# sram.net
KiCad netlist of a schematic drawn in Altium Designer
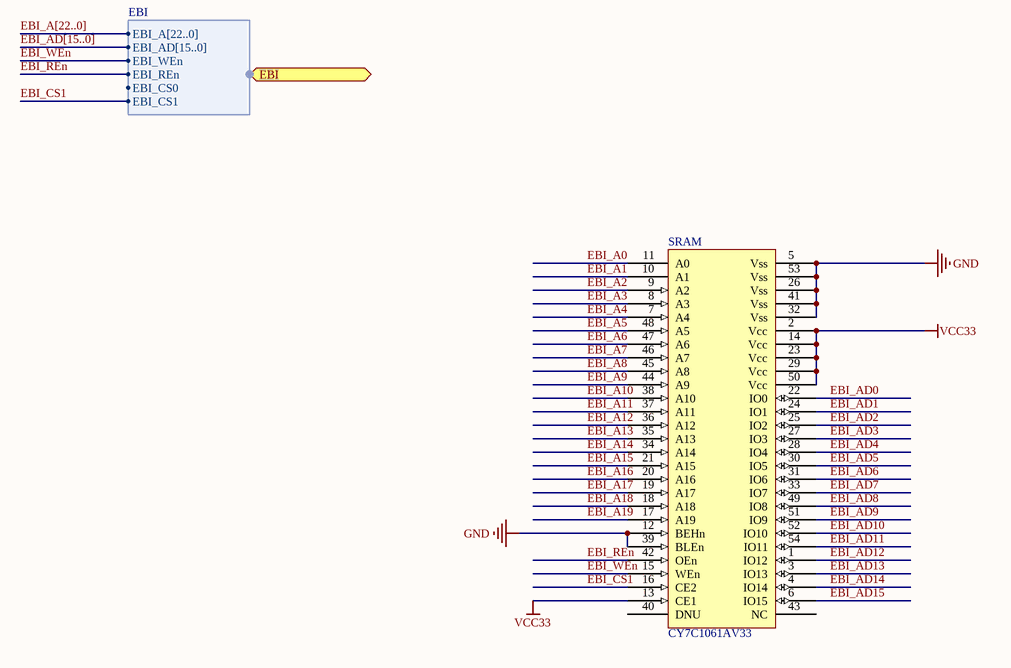
[diagram p0: sram.SchDoc]

(export (version "E")
  (design (tool "Eeschema 10.0.6"))
  (components
    (comp (ref "SRAM")
      (value "CY7C1061AV33")
      (footprint "CY7C1061AV33")
      (libsource (lib "SR10S3V3_Schematic") (part "CY7C1061AV33"))
    )
  )
  (nets
    (net (code "5") (name "/EBI_A0") (class "Default")
      (node (ref "SRAM") (pin "11") (pinfunction "A0_11") (pintype "passive"))
    )
    (net (code "6") (name "/EBI_A1") (class "Default")
      (node (ref "SRAM") (pin "10") (pinfunction "A1_10") (pintype "passive"))
    )
    (net (code "7") (name "/EBI_A2") (class "Default")
      (node (ref "SRAM") (pin "9") (pinfunction "A2_9") (pintype "input"))
    )
    (net (code "8") (name "/EBI_A3") (class "Default")
      (node (ref "SRAM") (pin "8") (pinfunction "A3_8") (pintype "input"))
    )
    (net (code "9") (name "/EBI_A4") (class "Default")
      (node (ref "SRAM") (pin "7") (pinfunction "A4_7") (pintype "input"))
    )
    (net (code "10") (name "/EBI_A5") (class "Default")
      (node (ref "SRAM") (pin "48") (pinfunction "A5_48") (pintype "input"))
    )
    (net (code "11") (name "/EBI_A6") (class "Default")
      (node (ref "SRAM") (pin "47") (pinfunction "A6_47") (pintype "input"))
    )
    (net (code "12") (name "/EBI_A7") (class "Default")
      (node (ref "SRAM") (pin "46") (pinfunction "A7_46") (pintype "input"))
    )
    (net (code "13") (name "/EBI_A8") (class "Default")
      (node (ref "SRAM") (pin "45") (pinfunction "A8_45") (pintype "input"))
    )
    (net (code "14") (name "/EBI_A9") (class "Default")
      (node (ref "SRAM") (pin "44") (pinfunction "A9_44") (pintype "input"))
    )
    (net (code "15") (name "/EBI_A10") (class "Default")
      (node (ref "SRAM") (pin "38") (pinfunction "A10_38") (pintype "input"))
    )
    (net (code "16") (name "/EBI_A11") (class "Default")
      (node (ref "SRAM") (pin "37") (pinfunction "A11_37") (pintype "input"))
    )
    (net (code "17") (name "/EBI_A12") (class "Default")
      (node (ref "SRAM") (pin "36") (pinfunction "A12_36") (pintype "input"))
    )
    (net (code "18") (name "/EBI_A13") (class "Default")
      (node (ref "SRAM") (pin "35") (pinfunction "A13_35") (pintype "input"))
    )
    (net (code "19") (name "/EBI_A14") (class "Default")
      (node (ref "SRAM") (pin "34") (pinfunction "A14_34") (pintype "input"))
    )
    (net (code "20") (name "/EBI_A15") (class "Default")
      (node (ref "SRAM") (pin "21") (pinfunction "A15_21") (pintype "input"))
    )
    (net (code "21") (name "/EBI_A16") (class "Default")
      (node (ref "SRAM") (pin "20") (pinfunction "A16_20") (pintype "input"))
    )
    (net (code "22") (name "/EBI_A17") (class "Default")
      (node (ref "SRAM") (pin "19") (pinfunction "A17_19") (pintype "input"))
    )
    (net (code "23") (name "/EBI_A18") (class "Default")
      (node (ref "SRAM") (pin "18") (pinfunction "A18_18") (pintype "input"))
    )
    (net (code "24") (name "/EBI_A19") (class "Default")
      (node (ref "SRAM") (pin "17") (pinfunction "A19_17") (pintype "input"))
    )
    (net (code "25") (name "/EBI_AD0") (class "Default")
      (node (ref "SRAM") (pin "22") (pinfunction "IO0_22") (pintype "bidirectional"))
    )
    (net (code "26") (name "/EBI_AD1") (class "Default")
      (node (ref "SRAM") (pin "24") (pinfunction "IO1_24") (pintype "bidirectional"))
    )
    (net (code "27") (name "/EBI_AD2") (class "Default")
      (node (ref "SRAM") (pin "25") (pinfunction "IO2_25") (pintype "bidirectional"))
    )
    (net (code "28") (name "/EBI_AD3") (class "Default")
      (node (ref "SRAM") (pin "27") (pinfunction "IO3_27") (pintype "bidirectional"))
    )
    (net (code "29") (name "/EBI_AD4") (class "Default")
      (node (ref "SRAM") (pin "28") (pinfunction "IO4_28") (pintype "bidirectional"))
    )
    (net (code "30") (name "/EBI_AD5") (class "Default")
      (node (ref "SRAM") (pin "30") (pinfunction "IO5_30") (pintype "bidirectional"))
    )
    (net (code "31") (name "/EBI_AD6") (class "Default")
      (node (ref "SRAM") (pin "31") (pinfunction "IO6_31") (pintype "bidirectional"))
    )
    (net (code "32") (name "/EBI_AD7") (class "Default")
      (node (ref "SRAM") (pin "33") (pinfunction "IO7_33") (pintype "bidirectional"))
    )
    (net (code "33") (name "/EBI_AD8") (class "Default")
      (node (ref "SRAM") (pin "49") (pinfunction "IO8_49") (pintype "bidirectional"))
    )
    (net (code "34") (name "/EBI_AD9") (class "Default")
      (node (ref "SRAM") (pin "51") (pinfunction "IO9_51") (pintype "bidirectional"))
    )
    (net (code "35") (name "/EBI_AD10") (class "Default")
      (node (ref "SRAM") (pin "52") (pinfunction "IO10_52") (pintype "bidirectional"))
    )
    (net (code "36") (name "/EBI_AD11") (class "Default")
      (node (ref "SRAM") (pin "54") (pinfunction "IO11_54") (pintype "bidirectional"))
    )
    (net (code "37") (name "/EBI_AD12") (class "Default")
      (node (ref "SRAM") (pin "1") (pinfunction "IO12_1") (pintype "bidirectional"))
    )
    (net (code "38") (name "/EBI_AD13") (class "Default")
      (node (ref "SRAM") (pin "3") (pinfunction "IO13_3") (pintype "bidirectional"))
    )
    (net (code "39") (name "/EBI_AD14") (class "Default")
      (node (ref "SRAM") (pin "4") (pinfunction "IO14_4") (pintype "bidirectional"))
    )
    (net (code "40") (name "/EBI_AD15") (class "Default")
      (node (ref "SRAM") (pin "6") (pinfunction "IO15_6") (pintype "bidirectional"))
    )
    (net (code "42") (name "/EBI_CS1") (class "Default")
      (node (ref "SRAM") (pin "16") (pinfunction "CE2_16") (pintype "input"))
    )
    (net (code "43") (name "/EBI_REn") (class "Default")
      (node (ref "SRAM") (pin "42") (pinfunction "OEn_42") (pintype "input"))
    )
    (net (code "44") (name "/EBI_WEn") (class "Default")
      (node (ref "SRAM") (pin "15") (pinfunction "WEn_15") (pintype "input"))
    )
    (net (code "47") (name "GND") (class "Default")
      (node (ref "SRAM") (pin "12") (pinfunction "BEHn_12") (pintype "input"))
      (node (ref "SRAM") (pin "26") (pinfunction "Vss_26") (pintype "power_in"))
      (node (ref "SRAM") (pin "32") (pinfunction "Vss_32") (pintype "power_in"))
      (node (ref "SRAM") (pin "39") (pinfunction "BLEn_39") (pintype "input"))
      (node (ref "SRAM") (pin "41") (pinfunction "Vss_41") (pintype "power_in"))
      (node (ref "SRAM") (pin "5") (pinfunction "Vss_5") (pintype "power_in"))
      (node (ref "SRAM") (pin "53") (pinfunction "Vss_53") (pintype "power_in"))
    )
    (net (code "48") (name "VCC33") (class "Default")
      (node (ref "SRAM") (pin "13") (pinfunction "CE1_13") (pintype "input"))
      (node (ref "SRAM") (pin "14") (pinfunction "Vcc_14") (pintype "power_in"))
      (node (ref "SRAM") (pin "2") (pinfunction "Vcc_2") (pintype "power_in"))
      (node (ref "SRAM") (pin "23") (pinfunction "Vcc_23") (pintype "power_in"))
      (node (ref "SRAM") (pin "29") (pinfunction "Vcc_29") (pintype "power_in"))
      (node (ref "SRAM") (pin "50") (pinfunction "Vcc_50") (pintype "power_in"))
    )
    (net (code "49") (name "unconnected-(SRAM-DNU-Pad40)") (class "Default")
      (node (ref "SRAM") (pin "40") (pinfunction "DNU_40") (pintype "passive"))
    )
    (net (code "50") (name "unconnected-(SRAM-NC-Pad43)") (class "Default")
      (node (ref "SRAM") (pin "43") (pinfunction "NC_43") (pintype "passive"))
    )
  )
)
